# electronic_load.net
KiCad netlist of a schematic drawn in EAGLE
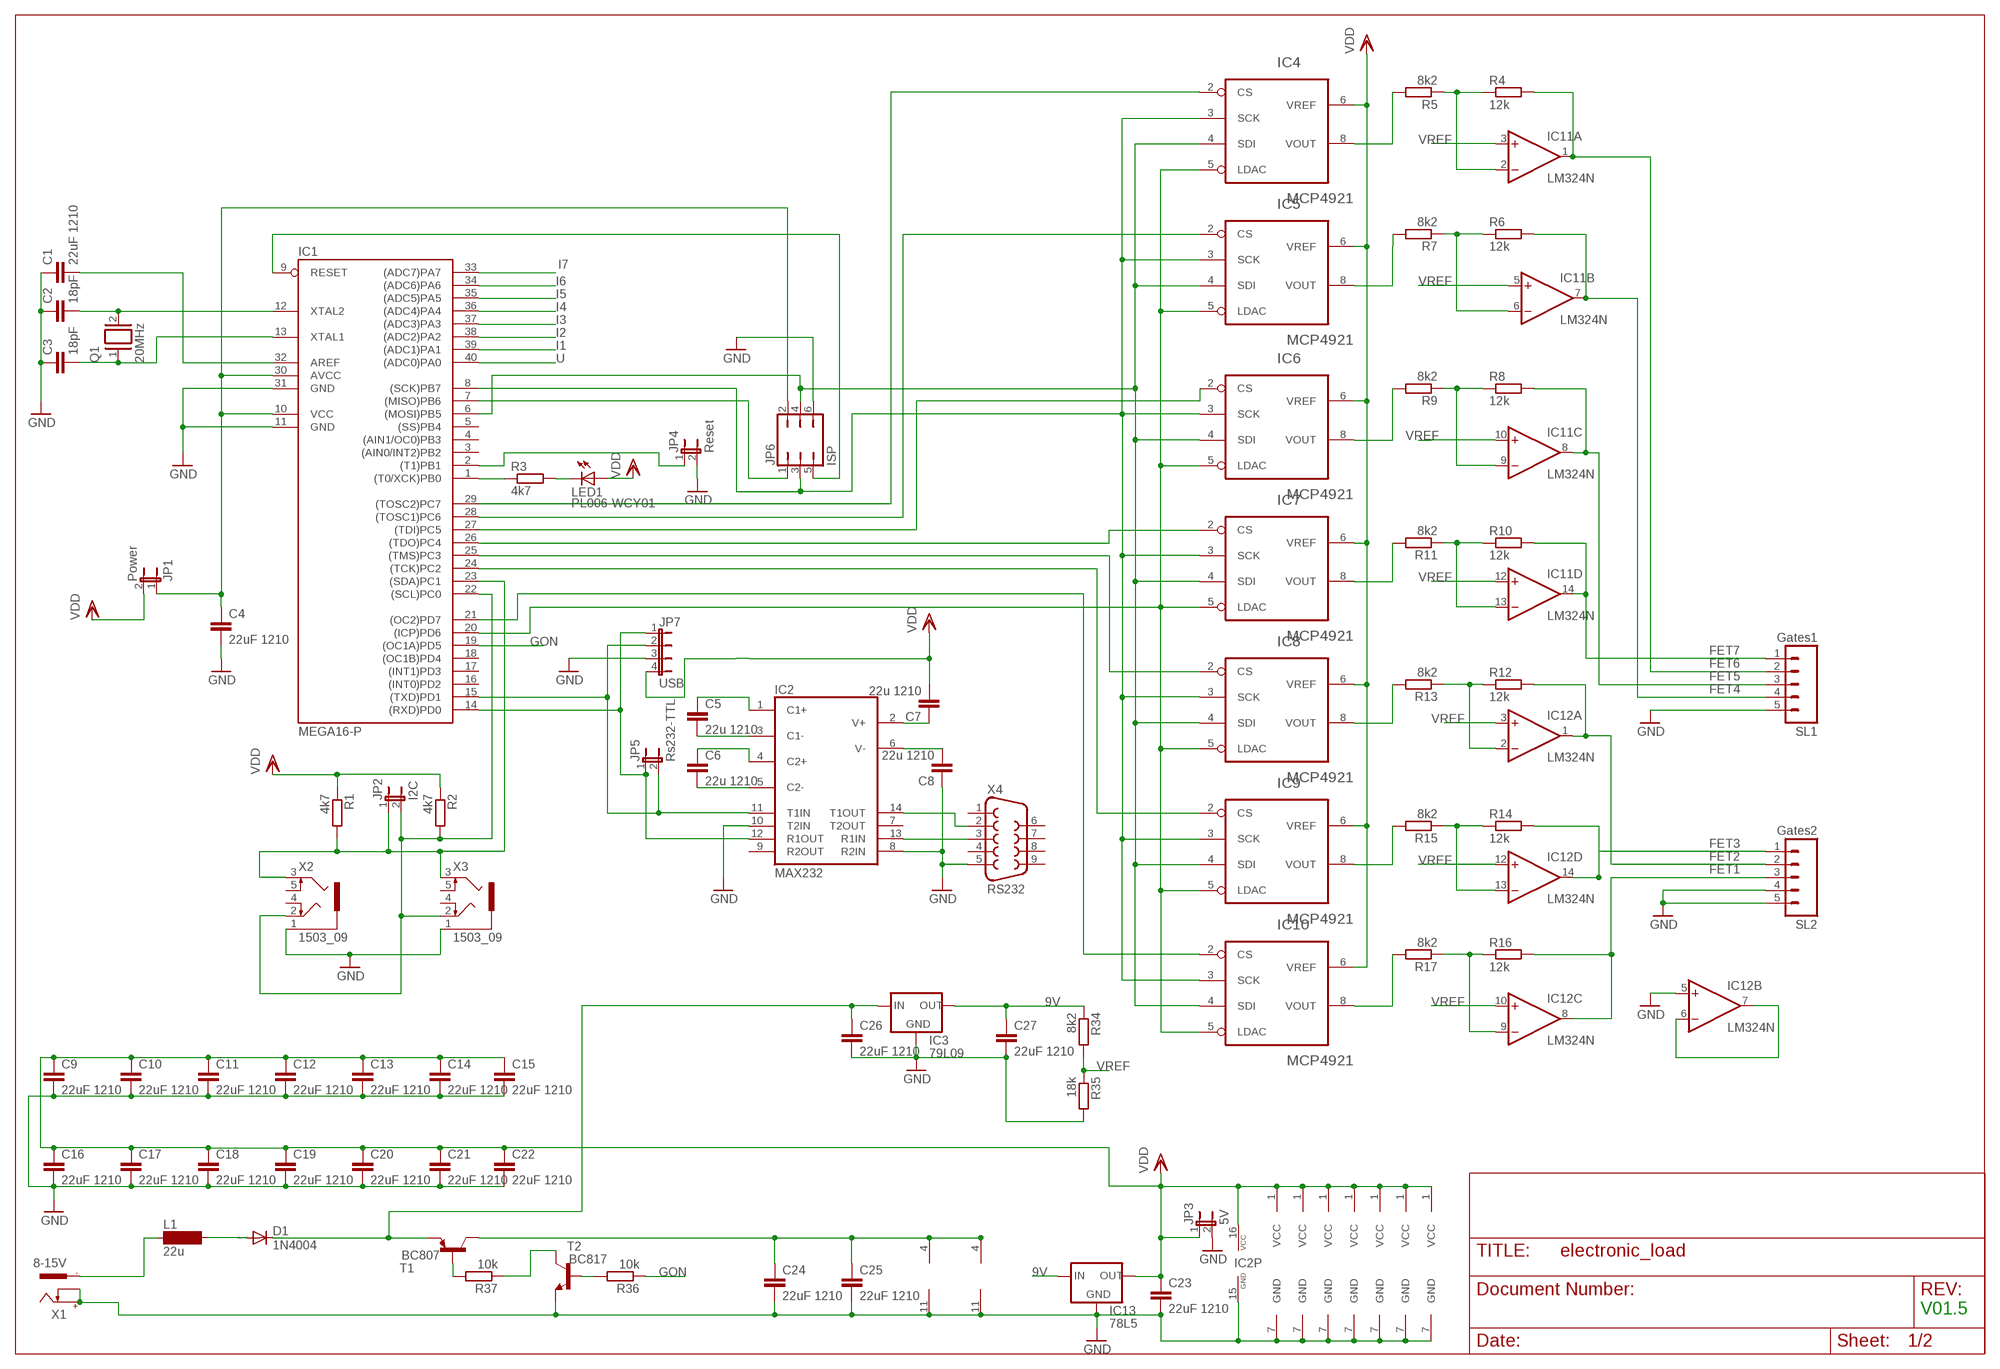
[diagram p0: schematic, sheet 1]
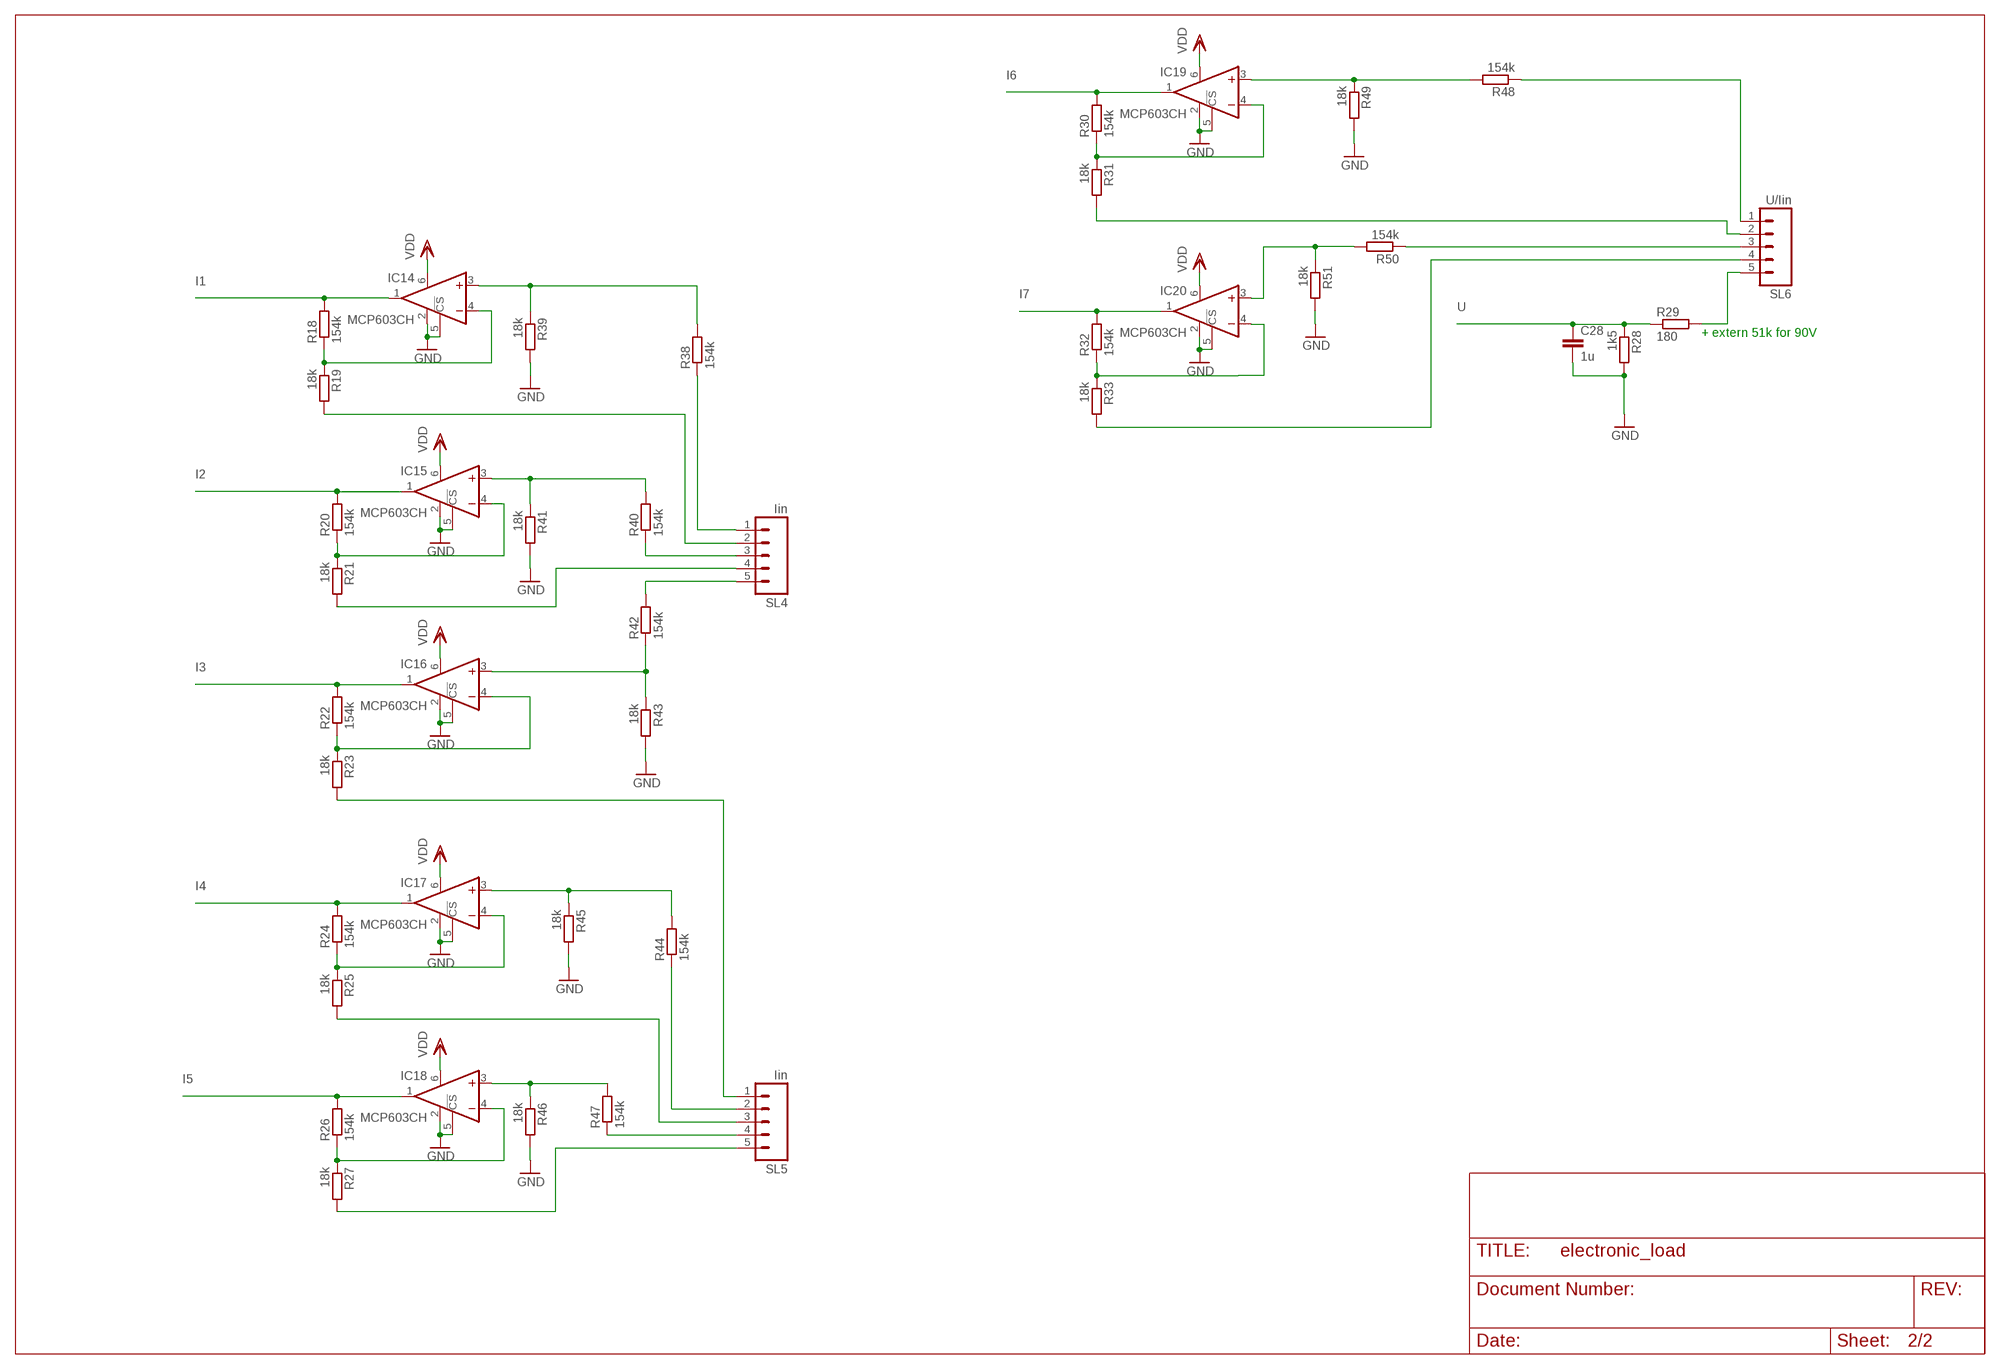
[diagram p1: schematic, sheet 2]

(export (version "E")
  (design (tool "Eeschema 10.0.6"))
  (components
    (comp (ref "C28")
      (value "1u")
      (footprint "eagle-import:C1206")
      (libsource (lib "eagle-import") (part "resistor_C-EUC1206"))
    )
    (comp (ref "IC14")
      (value "MCP603CH")
      (footprint "eagle-import:SOT23-6")
      (libsource (lib "eagle-import") (part "MCP603CH"))
    )
    (comp (ref "IC15")
      (value "MCP603CH")
      (footprint "eagle-import:SOT23-6")
      (libsource (lib "eagle-import") (part "MCP603CH"))
    )
    (comp (ref "IC16")
      (value "MCP603CH")
      (footprint "eagle-import:SOT23-6")
      (libsource (lib "eagle-import") (part "MCP603CH"))
    )
    (comp (ref "IC17")
      (value "MCP603CH")
      (footprint "eagle-import:SOT23-6")
      (libsource (lib "eagle-import") (part "MCP603CH"))
    )
    (comp (ref "IC18")
      (value "MCP603CH")
      (footprint "eagle-import:SOT23-6")
      (libsource (lib "eagle-import") (part "MCP603CH"))
    )
    (comp (ref "IC19")
      (value "MCP603CH")
      (footprint "eagle-import:SOT23-6")
      (libsource (lib "eagle-import") (part "MCP603CH"))
    )
    (comp (ref "IC20")
      (value "MCP603CH")
      (footprint "eagle-import:SOT23-6")
      (libsource (lib "eagle-import") (part "MCP603CH"))
    )
    (comp (ref "R18")
      (value "154k")
      (footprint "eagle-import:0207_2V")
      (libsource (lib "eagle-import") (part "R-EU_0207/2V"))
    )
    (comp (ref "R19")
      (value "18k")
      (footprint "eagle-import:0207_2V")
      (libsource (lib "eagle-import") (part "R-EU_0207/2V"))
    )
    (comp (ref "R20")
      (value "154k")
      (footprint "eagle-import:0207_2V")
      (libsource (lib "eagle-import") (part "R-EU_0207/2V"))
    )
    (comp (ref "R21")
      (value "18k")
      (footprint "eagle-import:0207_2V")
      (libsource (lib "eagle-import") (part "R-EU_0207/2V"))
    )
    (comp (ref "R22")
      (value "154k")
      (footprint "eagle-import:0207_2V")
      (libsource (lib "eagle-import") (part "R-EU_0207/2V"))
    )
    (comp (ref "R23")
      (value "18k")
      (footprint "eagle-import:0207_2V")
      (libsource (lib "eagle-import") (part "R-EU_0207/2V"))
    )
    (comp (ref "R24")
      (value "154k")
      (footprint "eagle-import:0207_2V")
      (libsource (lib "eagle-import") (part "R-EU_0207/2V"))
    )
    (comp (ref "R25")
      (value "18k")
      (footprint "eagle-import:0207_2V")
      (libsource (lib "eagle-import") (part "R-EU_0207/2V"))
    )
    (comp (ref "R26")
      (value "154k")
      (footprint "eagle-import:0207_2V")
      (libsource (lib "eagle-import") (part "R-EU_0207/2V"))
    )
    (comp (ref "R27")
      (value "18k")
      (footprint "eagle-import:0207_2V")
      (libsource (lib "eagle-import") (part "R-EU_0207/2V"))
    )
    (comp (ref "R28")
      (value "1k5")
      (footprint "eagle-import:R1206")
      (libsource (lib "eagle-import") (part "R-EU_R1206"))
    )
    (comp (ref "R29")
      (value "180")
      (footprint "eagle-import:R1206")
      (libsource (lib "eagle-import") (part "R-EU_R1206"))
    )
    (comp (ref "R30")
      (value "154k")
      (footprint "eagle-import:0207_2V")
      (libsource (lib "eagle-import") (part "R-EU_0207/2V"))
    )
    (comp (ref "R31")
      (value "18k")
      (footprint "eagle-import:0207_2V")
      (libsource (lib "eagle-import") (part "R-EU_0207/2V"))
    )
    (comp (ref "R32")
      (value "154k")
      (footprint "eagle-import:0207_2V")
      (libsource (lib "eagle-import") (part "R-EU_0207/2V"))
    )
    (comp (ref "R33")
      (value "18k")
      (footprint "eagle-import:0207_2V")
      (libsource (lib "eagle-import") (part "R-EU_0207/2V"))
    )
    (comp (ref "R38")
      (value "154k")
      (footprint "eagle-import:0207_2V")
      (libsource (lib "eagle-import") (part "R-EU_0207/2V"))
    )
    (comp (ref "R39")
      (value "18k")
      (footprint "eagle-import:0207_2V")
      (libsource (lib "eagle-import") (part "R-EU_0207/2V"))
    )
    (comp (ref "R40")
      (value "154k")
      (footprint "eagle-import:0207_2V")
      (libsource (lib "eagle-import") (part "R-EU_0207/2V"))
    )
    (comp (ref "R41")
      (value "18k")
      (footprint "eagle-import:0207_2V")
      (libsource (lib "eagle-import") (part "R-EU_0207/2V"))
    )
    (comp (ref "R42")
      (value "154k")
      (footprint "eagle-import:0207_2V")
      (libsource (lib "eagle-import") (part "R-EU_0207/2V"))
    )
    (comp (ref "R43")
      (value "18k")
      (footprint "eagle-import:0207_2V")
      (libsource (lib "eagle-import") (part "R-EU_0207/2V"))
    )
    (comp (ref "R44")
      (value "154k")
      (footprint "eagle-import:0207_2V")
      (libsource (lib "eagle-import") (part "R-EU_0207/2V"))
    )
    (comp (ref "R45")
      (value "18k")
      (footprint "eagle-import:0207_2V")
      (libsource (lib "eagle-import") (part "R-EU_0207/2V"))
    )
    (comp (ref "R46")
      (value "18k")
      (footprint "eagle-import:0207_2V")
      (libsource (lib "eagle-import") (part "R-EU_0207/2V"))
    )
    (comp (ref "R47")
      (value "154k")
      (footprint "eagle-import:0207_2V")
      (libsource (lib "eagle-import") (part "R-EU_0207/2V"))
    )
    (comp (ref "R48")
      (value "154k")
      (footprint "eagle-import:0207_2V")
      (libsource (lib "eagle-import") (part "R-EU_0207/2V"))
    )
    (comp (ref "R49")
      (value "18k")
      (footprint "eagle-import:0207_2V")
      (libsource (lib "eagle-import") (part "R-EU_0207/2V"))
    )
    (comp (ref "R50")
      (value "154k")
      (footprint "eagle-import:0207_2V")
      (libsource (lib "eagle-import") (part "R-EU_0207/2V"))
    )
    (comp (ref "R51")
      (value "18k")
      (footprint "eagle-import:0207_2V")
      (libsource (lib "eagle-import") (part "R-EU_0207/2V"))
    )
    (comp (ref "SL4")
      (value "Iin")
      (footprint "eagle-import:05P")
      (libsource (lib "eagle-import") (part "M05"))
    )
    (comp (ref "SL5")
      (value "Iin")
      (footprint "eagle-import:05P")
      (libsource (lib "eagle-import") (part "M05"))
    )
    (comp (ref "SL6")
      (value "U/Iin")
      (footprint "eagle-import:05P")
      (libsource (lib "eagle-import") (part "M05"))
    )
    (comp (ref "C1")
      (value "22uF 1210")
      (footprint "eagle-import:C1206")
      (libsource (lib "eagle-import") (part "C-EUC1206"))
    )
    (comp (ref "C2")
      (value "18pF")
      (footprint "eagle-import:C025-025X050")
      (libsource (lib "eagle-import") (part "resistor_C-EU025-025X050"))
    )
    (comp (ref "C3")
      (value "18pF")
      (footprint "eagle-import:C025-025X050")
      (libsource (lib "eagle-import") (part "resistor_C-EU025-025X050"))
    )
    (comp (ref "C4")
      (value "22uF 1210")
      (footprint "eagle-import:C1206")
      (libsource (lib "eagle-import") (part "C-EUC1206"))
    )
    (comp (ref "C5")
      (value "22u 1210")
      (footprint "eagle-import:C1206")
      (libsource (lib "eagle-import") (part "C-EUC1206"))
    )
    (comp (ref "C6")
      (value "22u 1210")
      (footprint "eagle-import:C1206")
      (libsource (lib "eagle-import") (part "C-EUC1206"))
    )
    (comp (ref "C7")
      (value "22u 1210")
      (footprint "eagle-import:C1206")
      (libsource (lib "eagle-import") (part "C-EUC1206"))
    )
    (comp (ref "C8")
      (value "22u 1210")
      (footprint "eagle-import:C1206")
      (libsource (lib "eagle-import") (part "C-EUC1206"))
    )
    (comp (ref "C9")
      (value "22uF 1210")
      (footprint "eagle-import:C1206")
      (libsource (lib "eagle-import") (part "C-EUC1206"))
    )
    (comp (ref "C10")
      (value "22uF 1210")
      (footprint "eagle-import:C1206")
      (libsource (lib "eagle-import") (part "C-EUC1206"))
    )
    (comp (ref "C11")
      (value "22uF 1210")
      (footprint "eagle-import:C1206")
      (libsource (lib "eagle-import") (part "C-EUC1206"))
    )
    (comp (ref "C12")
      (value "22uF 1210")
      (footprint "eagle-import:C1206")
      (libsource (lib "eagle-import") (part "C-EUC1206"))
    )
    (comp (ref "C13")
      (value "22uF 1210")
      (footprint "eagle-import:C1206")
      (libsource (lib "eagle-import") (part "C-EUC1206"))
    )
    (comp (ref "C14")
      (value "22uF 1210")
      (footprint "eagle-import:C1206")
      (libsource (lib "eagle-import") (part "C-EUC1206"))
    )
    (comp (ref "C15")
      (value "22uF 1210")
      (footprint "eagle-import:C1206")
      (libsource (lib "eagle-import") (part "C-EUC1206"))
    )
    (comp (ref "C16")
      (value "22uF 1210")
      (footprint "eagle-import:C1206")
      (libsource (lib "eagle-import") (part "C-EUC1206"))
    )
    (comp (ref "C17")
      (value "22uF 1210")
      (footprint "eagle-import:C1206")
      (libsource (lib "eagle-import") (part "C-EUC1206"))
    )
    (comp (ref "C18")
      (value "22uF 1210")
      (footprint "eagle-import:C1206")
      (libsource (lib "eagle-import") (part "C-EUC1206"))
    )
    (comp (ref "C19")
      (value "22uF 1210")
      (footprint "eagle-import:C1206")
      (libsource (lib "eagle-import") (part "C-EUC1206"))
    )
    (comp (ref "C20")
      (value "22uF 1210")
      (footprint "eagle-import:C1206")
      (libsource (lib "eagle-import") (part "C-EUC1206"))
    )
    (comp (ref "C21")
      (value "22uF 1210")
      (footprint "eagle-import:C1206")
      (libsource (lib "eagle-import") (part "C-EUC1206"))
    )
    (comp (ref "C22")
      (value "22uF 1210")
      (footprint "eagle-import:C1206")
      (libsource (lib "eagle-import") (part "C-EUC1206"))
    )
    (comp (ref "C23")
      (value "22uF 1210")
      (footprint "eagle-import:C1206")
      (libsource (lib "eagle-import") (part "C-EUC1206"))
    )
    (comp (ref "C24")
      (value "22uF 1210")
      (footprint "eagle-import:C1206")
      (libsource (lib "eagle-import") (part "C-EUC1206"))
    )
    (comp (ref "C25")
      (value "22uF 1210")
      (footprint "eagle-import:C1206")
      (libsource (lib "eagle-import") (part "C-EUC1206"))
    )
    (comp (ref "C26")
      (value "22uF 1210")
      (footprint "eagle-import:C1206")
      (libsource (lib "eagle-import") (part "C-EUC1206"))
    )
    (comp (ref "C27")
      (value "22uF 1210")
      (footprint "eagle-import:C1206")
      (libsource (lib "eagle-import") (part "C-EUC1206"))
    )
    (comp (ref "D1")
      (value "1N4004")
      (footprint "eagle-import:DO41-10")
      (libsource (lib "eagle-import") (part "1N4004"))
    )
    (comp (ref "IC1")
      (value "MEGA16-P")
      (footprint "eagle-import:DIL40")
      (fields (field (name "MPN") "ATMEGA16-16PU"))
      (libsource (lib "eagle-import") (part "MEGA16-P"))
    )
    (comp (ref "IC2")
      (value "MAX232")
      (footprint "eagle-import:DIL16")
      (fields (field (name "MF") "MAXIM") (field (name "MPN") "MAX232ACPE+"))
      (libsource (lib "eagle-import") (part "MAX232"))
    )
    (comp (ref "IC3")
      (value "79L09")
      (footprint "eagle-import:78LXX")
      (libsource (lib "eagle-import") (part "78LXX"))
    )
    (comp (ref "IC4")
      (value "MCP4921")
      (footprint "eagle-import:DIL08")
      (libsource (lib "eagle-import") (part "MCP491"))
    )
    (comp (ref "IC5")
      (value "MCP4921")
      (footprint "eagle-import:DIL08")
      (libsource (lib "eagle-import") (part "MCP491"))
    )
    (comp (ref "IC6")
      (value "MCP4921")
      (footprint "eagle-import:DIL08")
      (libsource (lib "eagle-import") (part "MCP491"))
    )
    (comp (ref "IC7")
      (value "MCP4921")
      (footprint "eagle-import:DIL08")
      (libsource (lib "eagle-import") (part "MCP491"))
    )
    (comp (ref "IC8")
      (value "MCP4921")
      (footprint "eagle-import:DIL08")
      (libsource (lib "eagle-import") (part "MCP491"))
    )
    (comp (ref "IC9")
      (value "MCP4921")
      (footprint "eagle-import:DIL08")
      (libsource (lib "eagle-import") (part "MCP491"))
    )
    (comp (ref "IC10")
      (value "MCP4921")
      (footprint "eagle-import:DIL08")
      (libsource (lib "eagle-import") (part "MCP491"))
    )
    (comp (ref "IC11")
      (value "LM324N")
      (footprint "eagle-import:DIL14")
      (libsource (lib "eagle-import") (part "LM324N"))
    )
    (comp (ref "IC12")
      (value "LM324N")
      (footprint "eagle-import:DIL14")
      (libsource (lib "eagle-import") (part "LM324N"))
    )
    (comp (ref "IC13")
      (value "78L5")
      (footprint "eagle-import:78LXX")
      (libsource (lib "eagle-import") (part "78LXX"))
    )
    (comp (ref "JP1")
      (value "Power")
      (footprint "eagle-import:JP1")
      (libsource (lib "eagle-import") (part "JP1E"))
    )
    (comp (ref "JP2")
      (value "I2C")
      (footprint "eagle-import:JP1")
      (libsource (lib "eagle-import") (part "JP1E"))
    )
    (comp (ref "JP3")
      (value "5V")
      (footprint "eagle-import:JP1")
      (libsource (lib "eagle-import") (part "JP1E"))
    )
    (comp (ref "JP4")
      (value "Reset")
      (footprint "eagle-import:JP1")
      (libsource (lib "eagle-import") (part "JP1E"))
    )
    (comp (ref "JP5")
      (value "Rs232-TTL")
      (footprint "eagle-import:JP1")
      (libsource (lib "eagle-import") (part "JP1E"))
    )
    (comp (ref "JP6")
      (value "ISP")
      (footprint "eagle-import:JP3Q")
      (libsource (lib "eagle-import") (part "JP3Q"))
    )
    (comp (ref "JP7")
      (value "USB")
      (footprint "eagle-import:JP4")
      (libsource (lib "eagle-import") (part "JP4E"))
    )
    (comp (ref "L1")
      (value "22u")
      (footprint "eagle-import:MS85")
      (libsource (lib "eagle-import") (part "MS85"))
    )
    (comp (ref "LED1")
      (value "PL006-WCY01")
      (footprint "eagle-import:SOT23")
      (libsource (lib "eagle-import") (part "PL006-WCY01"))
    )
    (comp (ref "Q1")
      (value "20MHz")
      (footprint "eagle-import:QS")
      (libsource (lib "eagle-import") (part "XTAL/S"))
    )
    (comp (ref "R1")
      (value "4k7")
      (footprint "eagle-import:0207_2V")
      (libsource (lib "eagle-import") (part "R-EU_0207/2V"))
    )
    (comp (ref "R2")
      (value "4k7")
      (footprint "eagle-import:0207_2V")
      (libsource (lib "eagle-import") (part "R-EU_0207/2V"))
    )
    (comp (ref "R3")
      (value "4k7")
      (footprint "eagle-import:R1206")
      (libsource (lib "eagle-import") (part "R-EU_R1206"))
    )
    (comp (ref "R4")
      (value "12k")
      (footprint "eagle-import:R1206")
      (libsource (lib "eagle-import") (part "R-EU_R1206"))
    )
    (comp (ref "R5")
      (value "8k2")
      (footprint "eagle-import:R1206")
      (libsource (lib "eagle-import") (part "R-EU_R1206"))
    )
    (comp (ref "R6")
      (value "12k")
      (footprint "eagle-import:R1206")
      (libsource (lib "eagle-import") (part "R-EU_R1206"))
    )
    (comp (ref "R7")
      (value "8k2")
      (footprint "eagle-import:R1206")
      (libsource (lib "eagle-import") (part "R-EU_R1206"))
    )
    (comp (ref "R8")
      (value "12k")
      (footprint "eagle-import:R1206")
      (libsource (lib "eagle-import") (part "R-EU_R1206"))
    )
    (comp (ref "R9")
      (value "8k2")
      (footprint "eagle-import:R1206")
      (libsource (lib "eagle-import") (part "R-EU_R1206"))
    )
    (comp (ref "R10")
      (value "12k")
      (footprint "eagle-import:R1206")
      (libsource (lib "eagle-import") (part "R-EU_R1206"))
    )
    (comp (ref "R11")
      (value "8k2")
      (footprint "eagle-import:R1206")
      (libsource (lib "eagle-import") (part "R-EU_R1206"))
    )
    (comp (ref "R12")
      (value "12k")
      (footprint "eagle-import:R1206")
      (libsource (lib "eagle-import") (part "R-EU_R1206"))
    )
    (comp (ref "R13")
      (value "8k2")
      (footprint "eagle-import:R1206")
      (libsource (lib "eagle-import") (part "R-EU_R1206"))
    )
    (comp (ref "R14")
      (value "12k")
      (footprint "eagle-import:R1206")
      (libsource (lib "eagle-import") (part "R-EU_R1206"))
    )
    (comp (ref "R15")
      (value "8k2")
      (footprint "eagle-import:R1206")
      (libsource (lib "eagle-import") (part "R-EU_R1206"))
    )
    (comp (ref "R16")
      (value "12k")
      (footprint "eagle-import:R1206")
      (libsource (lib "eagle-import") (part "R-EU_R1206"))
    )
    (comp (ref "R17")
      (value "8k2")
      (footprint "eagle-import:R1206")
      (libsource (lib "eagle-import") (part "R-EU_R1206"))
    )
    (comp (ref "R34")
      (value "8k2")
      (footprint "eagle-import:R1206")
      (libsource (lib "eagle-import") (part "R-EU_R1206"))
    )
    (comp (ref "R35")
      (value "18k")
      (footprint "eagle-import:R1206")
      (libsource (lib "eagle-import") (part "R-EU_R1206"))
    )
    (comp (ref "R36")
      (value "10k")
      (footprint "eagle-import:R1206")
      (libsource (lib "eagle-import") (part "R-EU_R1206"))
    )
    (comp (ref "R37")
      (value "10k")
      (footprint "eagle-import:R1206")
      (libsource (lib "eagle-import") (part "R-EU_R1206"))
    )
    (comp (ref "SL1")
      (value "Gates1")
      (footprint "eagle-import:05P")
      (libsource (lib "eagle-import") (part "M05"))
    )
    (comp (ref "SL2")
      (value "Gates2")
      (footprint "eagle-import:05P")
      (libsource (lib "eagle-import") (part "M05"))
    )
    (comp (ref "T1")
      (value "BC807")
      (footprint "eagle-import:SOT23-BEC")
      (libsource (lib "eagle-import") (part "-PNP-SOT23-BECBC807-16"))
    )
    (comp (ref "T2")
      (value "BC817")
      (footprint "eagle-import:SOT23-BEC")
      (libsource (lib "eagle-import") (part "-NPN-SOT23-BECBC817-16"))
    )
    (comp (ref "X1")
      (value "8-15V")
      (footprint "eagle-import:737992-5")
      (libsource (lib "eagle-import") (part "737992-55"))
    )
    (comp (ref "X2")
      (value "1503_09")
      (footprint "eagle-import:1503_09")
      (libsource (lib "eagle-import") (part "1503_09"))
    )
    (comp (ref "X3")
      (value "1503_09")
      (footprint "eagle-import:1503_09")
      (libsource (lib "eagle-import") (part "1503_09"))
    )
    (comp (ref "X4")
      (value "RS232")
      (footprint "eagle-import:F09H")
      (libsource (lib "eagle-import") (part "F09H"))
    )
  )
  (nets
    (net (code "1") (name "9V") (class "Default")
      (node (ref "C27") (pin "1") (pinfunction "1_1") (pintype "passive"))
      (node (ref "IC13") (pin "IN") (pinfunction "IN_IN") (pintype "input"))
      (node (ref "IC3") (pin "OUT") (pinfunction "OUT_OUT") (pintype "passive"))
      (node (ref "R34") (pin "1") (pinfunction "1_1") (pintype "passive"))
    )
    (net (code "2") (name "FET1") (class "Default")
      (node (ref "IC12") (pin "8") (pinfunction "OUT_8") (pintype "output"))
      (node (ref "R16") (pin "2") (pinfunction "2_2") (pintype "passive"))
      (node (ref "SL2") (pin "3") (pinfunction "3_3") (pintype "passive"))
    )
    (net (code "3") (name "FET2") (class "Default")
      (node (ref "IC12") (pin "1") (pinfunction "OUT_1") (pintype "output"))
      (node (ref "R12") (pin "2") (pinfunction "2_2") (pintype "passive"))
      (node (ref "SL2") (pin "2") (pinfunction "2_2") (pintype "passive"))
    )
    (net (code "4") (name "FET3") (class "Default")
      (node (ref "IC12") (pin "14") (pinfunction "OUT_14") (pintype "output"))
      (node (ref "R14") (pin "2") (pinfunction "2_2") (pintype "passive"))
      (node (ref "SL2") (pin "1") (pinfunction "1_1") (pintype "passive"))
    )
    (net (code "5") (name "FET4") (class "Default")
      (node (ref "IC11") (pin "7") (pinfunction "OUT_7") (pintype "output"))
      (node (ref "R6") (pin "2") (pinfunction "2_2") (pintype "passive"))
      (node (ref "SL1") (pin "4") (pinfunction "4_4") (pintype "passive"))
    )
    (net (code "6") (name "FET5") (class "Default")
      (node (ref "IC11") (pin "8") (pinfunction "OUT_8") (pintype "output"))
      (node (ref "R8") (pin "2") (pinfunction "2_2") (pintype "passive"))
      (node (ref "SL1") (pin "3") (pinfunction "3_3") (pintype "passive"))
    )
    (net (code "7") (name "FET6") (class "Default")
      (node (ref "IC11") (pin "1") (pinfunction "OUT_1") (pintype "output"))
      (node (ref "R4") (pin "2") (pinfunction "2_2") (pintype "passive"))
      (node (ref "SL1") (pin "2") (pinfunction "2_2") (pintype "passive"))
    )
    (net (code "8") (name "FET7") (class "Default")
      (node (ref "IC11") (pin "14") (pinfunction "OUT_14") (pintype "output"))
      (node (ref "R10") (pin "2") (pinfunction "2_2") (pintype "passive"))
      (node (ref "SL1") (pin "1") (pinfunction "1_1") (pintype "passive"))
    )
    (net (code "9") (name "GND") (class "Default")
      (node (ref "C1") (pin "1") (pinfunction "1_1") (pintype "passive"))
      (node (ref "C10") (pin "2") (pinfunction "2_2") (pintype "passive"))
      (node (ref "C11") (pin "2") (pinfunction "2_2") (pintype "passive"))
      (node (ref "C12") (pin "2") (pinfunction "2_2") (pintype "passive"))
      (node (ref "C13") (pin "2") (pinfunction "2_2") (pintype "passive"))
      (node (ref "C14") (pin "2") (pinfunction "2_2") (pintype "passive"))
      (node (ref "C15") (pin "2") (pinfunction "2_2") (pintype "passive"))
      (node (ref "C16") (pin "2") (pinfunction "2_2") (pintype "passive"))
      (node (ref "C17") (pin "2") (pinfunction "2_2") (pintype "passive"))
      (node (ref "C18") (pin "2") (pinfunction "2_2") (pintype "passive"))
      (node (ref "C19") (pin "2") (pinfunction "2_2") (pintype "passive"))
      (node (ref "C2") (pin "1") (pinfunction "1_1") (pintype "passive"))
      (node (ref "C20") (pin "2") (pinfunction "2_2") (pintype "passive"))
      (node (ref "C21") (pin "2") (pinfunction "2_2") (pintype "passive"))
      (node (ref "C22") (pin "2") (pinfunction "2_2") (pintype "passive"))
      (node (ref "C23") (pin "2") (pinfunction "2_2") (pintype "passive"))
      (node (ref "C24") (pin "2") (pinfunction "2_2") (pintype "passive"))
      (node (ref "C25") (pin "2") (pinfunction "2_2") (pintype "passive"))
      (node (ref "C26") (pin "2") (pinfunction "2_2") (pintype "passive"))
      (node (ref "C27") (pin "2") (pinfunction "2_2") (pintype "passive"))
      (node (ref "C28") (pin "2") (pinfunction "2_2") (pintype "passive"))
      (node (ref "C3") (pin "1") (pinfunction "1_1") (pintype "passive"))
      (node (ref "C4") (pin "2") (pinfunction "2_2") (pintype "passive"))
      (node (ref "C8") (pin "1") (pinfunction "1_1") (pintype "passive"))
      (node (ref "C9") (pin "2") (pinfunction "2_2") (pintype "passive"))
      (node (ref "IC1") (pin "11") (pinfunction "GND_11") (pintype "power_in"))
      (node (ref "IC1") (pin "31") (pinfunction "GND_31") (pintype "power_in"))
      (node (ref "IC10") (pin "7") (pinfunction "GND_7") (pintype "power_in"))
      (node (ref "IC11") (pin "11") (pinfunction "V-_11") (pintype "power_in"))
      (node (ref "IC12") (pin "11") (pinfunction "V-_11") (pintype "power_in"))
      (node (ref "IC12") (pin "5") (pinfunction "+IN_5") (pintype "input"))
      (node (ref "IC13") (pin "GND") (pinfunction "GND_GND") (pintype "input"))
      (node (ref "IC14") (pin "2") (pinfunction "V-_2") (pintype "power_in"))
      (node (ref "IC14") (pin "5") (pinfunction "~{CS}_5") (pintype "input"))
      (node (ref "IC15") (pin "2") (pinfunction "V-_2") (pintype "power_in"))
      (node (ref "IC15") (pin "5") (pinfunction "~{CS}_5") (pintype "input"))
      (node (ref "IC16") (pin "2") (pinfunction "V-_2") (pintype "power_in"))
      (node (ref "IC16") (pin "5") (pinfunction "~{CS}_5") (pintype "input"))
      (node (ref "IC17") (pin "2") (pinfunction "V-_2") (pintype "power_in"))
      (node (ref "IC17") (pin "5") (pinfunction "~{CS}_5") (pintype "input"))
      (node (ref "IC18") (pin "2") (pinfunction "V-_2") (pintype "power_in"))
      (node (ref "IC18") (pin "5") (pinfunction "~{CS}_5") (pintype "input"))
      (node (ref "IC19") (pin "2") (pinfunction "V-_2") (pintype "power_in"))
      (node (ref "IC19") (pin "5") (pinfunction "~{CS}_5") (pintype "input"))
      (node (ref "IC2") (pin "10") (pinfunction "T2IN_10") (pintype "input"))
      (node (ref "IC2") (pin "15") (pinfunction "GND_15") (pintype "power_in"))
      (node (ref "IC2") (pin "8") (pinfunction "R2IN_8") (pintype "input"))
      (node (ref "IC20") (pin "2") (pinfunction "V-_2") (pintype "power_in"))
      (node (ref "IC20") (pin "5") (pinfunction "~{CS}_5") (pintype "input"))
      (node (ref "IC3") (pin "GND") (pinfunction "GND_GND") (pintype "input"))
      (node (ref "IC4") (pin "7") (pinfunction "GND_7") (pintype "power_in"))
      (node (ref "IC5") (pin "7") (pinfunction "GND_7") (pintype "power_in"))
      (node (ref "IC6") (pin "7") (pinfunction "GND_7") (pintype "power_in"))
      (node (ref "IC7") (pin "7") (pinfunction "GND_7") (pintype "power_in"))
      (node (ref "IC8") (pin "7") (pinfunction "GND_7") (pintype "power_in"))
      (node (ref "IC9") (pin "7") (pinfunction "GND_7") (pintype "power_in"))
      (node (ref "JP3") (pin "2") (pinfunction "2_2") (pintype "passive"))
      (node (ref "JP4") (pin "2") (pinfunction "2_2") (pintype "passive"))
      (node (ref "JP6") (pin "6") (pinfunction "6_6") (pintype "passive"))
      (node (ref "JP7") (pin "3") (pinfunction "3_3") (pintype "passive"))
      (node (ref "R28") (pin "2") (pinfunction "2_2") (pintype "passive"))
      (node (ref "R35") (pin "2") (pinfunction "2_2") (pintype "passive"))
      (node (ref "R39") (pin "2") (pinfunction "2_2") (pintype "passive"))
      (node (ref "R41") (pin "2") (pinfunction "2_2") (pintype "passive"))
      (node (ref "R43") (pin "2") (pinfunction "2_2") (pintype "passive"))
      (node (ref "R45") (pin "2") (pinfunction "2_2") (pintype "passive"))
      (node (ref "R46") (pin "2") (pinfunction "2_2") (pintype "passive"))
      (node (ref "R49") (pin "2") (pinfunction "2_2") (pintype "passive"))
      (node (ref "R51") (pin "2") (pinfunction "2_2") (pintype "passive"))
      (node (ref "SL1") (pin "5") (pinfunction "5_5") (pintype "passive"))
      (node (ref "SL2") (pin "4") (pinfunction "4_4") (pintype "passive"))
      (node (ref "SL2") (pin "5") (pinfunction "5_5") (pintype "passive"))
      (node (ref "T2") (pin "E") (pinfunction "E_E") (pintype "passive"))
      (node (ref "X1") (pin "+") (pinfunction "+_+") (pintype "passive"))
      (node (ref "X1") (pin "K") (pinfunction "K_K") (pintype "passive"))
      (node (ref "X2") (pin "1") (pinfunction "1_1") (pintype "passive"))
      (node (ref "X3") (pin "1") (pinfunction "1_1") (pintype "passive"))
      (node (ref "X4") (pin "5") (pinfunction "5_5") (pintype "passive"))
    )
    (net (code "10") (name "GON") (class "Default")
      (node (ref "IC1") (pin "19") (pinfunction "(OC1A)PD5_19") (pintype "bidirectional"))
      (node (ref "R36") (pin "1") (pinfunction "1_1") (pintype "passive"))
    )
    (net (code "11") (name "I1") (class "Default")
      (node (ref "IC1") (pin "39") (pinfunction "(ADC1)PA1_39") (pintype "bidirectional"))
      (node (ref "IC14") (pin "1") (pinfunction "OUT_1") (pintype "output"))
      (node (ref "R18") (pin "2") (pinfunction "2_2") (pintype "passive"))
    )
    (net (code "12") (name "I2") (class "Default")
      (node (ref "IC1") (pin "38") (pinfunction "(ADC2)PA2_38") (pintype "bidirectional"))
      (node (ref "IC15") (pin "1") (pinfunction "OUT_1") (pintype "output"))
      (node (ref "R20") (pin "2") (pinfunction "2_2") (pintype "passive"))
    )
    (net (code "13") (name "I3") (class "Default")
      (node (ref "IC1") (pin "37") (pinfunction "(ADC3)PA3_37") (pintype "bidirectional"))
      (node (ref "IC16") (pin "1") (pinfunction "OUT_1") (pintype "output"))
      (node (ref "R22") (pin "2") (pinfunction "2_2") (pintype "passive"))
    )
    (net (code "14") (name "I4") (class "Default")
      (node (ref "IC1") (pin "36") (pinfunction "(ADC4)PA4_36") (pintype "bidirectional"))
      (node (ref "IC17") (pin "1") (pinfunction "OUT_1") (pintype "output"))
      (node (ref "R24") (pin "2") (pinfunction "2_2") (pintype "passive"))
    )
    (net (code "15") (name "I5") (class "Default")
      (node (ref "IC1") (pin "35") (pinfunction "(ADC5)PA5_35") (pintype "bidirectional"))
      (node (ref "IC18") (pin "1") (pinfunction "OUT_1") (pintype "output"))
      (node (ref "R26") (pin "2") (pinfunction "2_2") (pintype "passive"))
    )
    (net (code "16") (name "I6") (class "Default")
      (node (ref "IC1") (pin "34") (pinfunction "(ADC6)PA6_34") (pintype "bidirectional"))
      (node (ref "IC19") (pin "1") (pinfunction "OUT_1") (pintype "output"))
      (node (ref "R30") (pin "2") (pinfunction "2_2") (pintype "passive"))
    )
    (net (code "17") (name "I7") (class "Default")
      (node (ref "IC1") (pin "33") (pinfunction "(ADC7)PA7_33") (pintype "bidirectional"))
      (node (ref "IC20") (pin "1") (pinfunction "OUT_1") (pintype "output"))
      (node (ref "R32") (pin "2") (pinfunction "2_2") (pintype "passive"))
    )
    (net (code "18") (name "Net-(C26-Pad1)") (class "Default")
      (node (ref "C26") (pin "1") (pinfunction "1_1") (pintype "passive"))
      (node (ref "D1") (pin "C") (pinfunction "C_C") (pintype "passive"))
      (node (ref "IC3") (pin "IN") (pinfunction "IN_IN") (pintype "input"))
      (node (ref "T1") (pin "E") (pinfunction "E_E") (pintype "passive"))
    )
    (net (code "19") (name "Net-(D1-PadA)") (class "Default")
      (node (ref "D1") (pin "A") (pinfunction "A_A") (pintype "passive"))
      (node (ref "L1") (pin "2") (pinfunction "2_2") (pintype "passive"))
    )
    (net (code "20") (name "Net-(IC1-(ICP)PD6)") (class "Default")
      (node (ref "IC1") (pin "20") (pinfunction "(ICP)PD6_20") (pintype "bidirectional"))
      (node (ref "IC10") (pin "5") (pinfunction "LDAC_5") (pintype "input"))
      (node (ref "IC4") (pin "5") (pinfunction "LDAC_5") (pintype "input"))
      (node (ref "IC5") (pin "5") (pinfunction "LDAC_5") (pintype "input"))
      (node (ref "IC6") (pin "5") (pinfunction "LDAC_5") (pintype "input"))
      (node (ref "IC7") (pin "5") (pinfunction "LDAC_5") (pintype "input"))
      (node (ref "IC8") (pin "5") (pinfunction "LDAC_5") (pintype "input"))
      (node (ref "IC9") (pin "5") (pinfunction "LDAC_5") (pintype "input"))
    )
    (net (code "21") (name "Net-(IC1-(MISO)PB6)") (class "Default")
      (node (ref "IC1") (pin "7") (pinfunction "(MISO)PB6_7") (pintype "bidirectional"))
      (node (ref "JP6") (pin "1") (pinfunction "1_1") (pintype "passive"))
    )
    (net (code "22") (name "Net-(IC1-(MOSI)PB5)") (class "Default")
      (node (ref "IC1") (pin "6") (pinfunction "(MOSI)PB5_6") (pintype "bidirectional"))
      (node (ref "IC10") (pin "4") (pinfunction "SDI_4") (pintype "input"))
      (node (ref "IC4") (pin "4") (pinfunction "SDI_4") (pintype "input"))
      (node (ref "IC5") (pin "4") (pinfunction "SDI_4") (pintype "input"))
      (node (ref "IC6") (pin "4") (pinfunction "SDI_4") (pintype "input"))
      (node (ref "IC7") (pin "4") (pinfunction "SDI_4") (pintype "input"))
      (node (ref "IC8") (pin "4") (pinfunction "SDI_4") (pintype "input"))
      (node (ref "IC9") (pin "4") (pinfunction "SDI_4") (pintype "input"))
      (node (ref "JP6") (pin "4") (pinfunction "4_4") (pintype "passive"))
    )
    (net (code "23") (name "Net-(IC1-(OC2)PD7)") (class "Default")
      (node (ref "IC1") (pin "21") (pinfunction "(OC2)PD7_21") (pintype "bidirectional"))
      (node (ref "IC10") (pin "2") (pinfunction "CS_2") (pintype "input"))
    )
    (net (code "24") (name "Net-(IC1-(RXD)PD0)") (class "Default")
      (node (ref "IC1") (pin "14") (pinfunction "(RXD)PD0_14") (pintype "bidirectional"))
      (node (ref "IC2") (pin "12") (pinfunction "R1OUT_12") (pintype "output"))
      (node (ref "JP5") (pin "1") (pinfunction "1_1") (pintype "passive"))
      (node (ref "JP7") (pin "1") (pinfunction "1_1") (pintype "passive"))
    )
    (net (code "25") (name "Net-(IC1-(SCK)PB7)") (class "Default")
      (node (ref "IC1") (pin "8") (pinfunction "(SCK)PB7_8") (pintype "bidirectional"))
      (node (ref "IC10") (pin "3") (pinfunction "SCK_3") (pintype "input"))
      (node (ref "IC4") (pin "3") (pinfunction "SCK_3") (pintype "input"))
      (node (ref "IC5") (pin "3") (pinfunction "SCK_3") (pintype "input"))
      (node (ref "IC6") (pin "3") (pinfunction "SCK_3") (pintype "input"))
      (node (ref "IC7") (pin "3") (pinfunction "SCK_3") (pintype "input"))
      (node (ref "IC8") (pin "3") (pinfunction "SCK_3") (pintype "input"))
      (node (ref "IC9") (pin "3") (pinfunction "SCK_3") (pintype "input"))
      (node (ref "JP6") (pin "3") (pinfunction "3_3") (pintype "passive"))
    )
    (net (code "26") (name "Net-(IC1-(SCL)PC0)") (class "Default")
      (node (ref "IC1") (pin "22") (pinfunction "(SCL)PC0_22") (pintype "bidirectional"))
      (node (ref "JP2") (pin "2") (pinfunction "2_2") (pintype "passive"))
      (node (ref "R2") (pin "2") (pinfunction "2_2") (pintype "passive"))
      (node (ref "X2") (pin "2") (pinfunction "2_2") (pintype "passive"))
      (node (ref "X3") (pin "2") (pinfunction "2_2") (pintype "passive"))
    )
    (net (code "27") (name "Net-(IC1-(SDA)PC1)") (class "Default")
      (node (ref "IC1") (pin "23") (pinfunction "(SDA)PC1_23") (pintype "bidirectional"))
      (node (ref "JP2") (pin "1") (pinfunction "1_1") (pintype "passive"))
      (node (ref "R1") (pin "2") (pinfunction "2_2") (pintype "passive"))
      (node (ref "X2") (pin "3") (pinfunction "3_3") (pintype "passive"))
      (node (ref "X3") (pin "3") (pinfunction "3_3") (pintype "passive"))
    )
    (net (code "28") (name "Net-(IC1-(T0{slash}XCK)PB0)") (class "Default")
      (node (ref "IC1") (pin "1") (pinfunction "(T0/XCK)PB0_1") (pintype "bidirectional"))
      (node (ref "R3") (pin "1") (pinfunction "1_1") (pintype "passive"))
    )
    (net (code "29") (name "Net-(IC1-(T1)PB1)") (class "Default")
      (node (ref "IC1") (pin "2") (pinfunction "(T1)PB1_2") (pintype "bidirectional"))
      (node (ref "JP4") (pin "1") (pinfunction "1_1") (pintype "passive"))
    )
    (net (code "30") (name "Net-(IC1-(TCK)PC2)") (class "Default")
      (node (ref "IC1") (pin "24") (pinfunction "(TCK)PC2_24") (pintype "bidirectional"))
      (node (ref "IC9") (pin "2") (pinfunction "CS_2") (pintype "input"))
    )
    (net (code "31") (name "Net-(IC1-(TDI)PC5)") (class "Default")
      (node (ref "IC1") (pin "27") (pinfunction "(TDI)PC5_27") (pintype "bidirectional"))
      (node (ref "IC6") (pin "2") (pinfunction "CS_2") (pintype "input"))
    )
    (net (code "32") (name "Net-(IC1-(TDO)PC4)") (class "Default")
      (node (ref "IC1") (pin "26") (pinfunction "(TDO)PC4_26") (pintype "bidirectional"))
      (node (ref "IC7") (pin "2") (pinfunction "CS_2") (pintype "input"))
    )
    (net (code "33") (name "Net-(IC1-(TMS)PC3)") (class "Default")
      (node (ref "IC1") (pin "25") (pinfunction "(TMS)PC3_25") (pintype "bidirectional"))
      (node (ref "IC8") (pin "2") (pinfunction "CS_2") (pintype "input"))
    )
    (net (code "34") (name "Net-(IC1-(TOSC1)PC6)") (class "Default")
      (node (ref "IC1") (pin "28") (pinfunction "(TOSC1)PC6_28") (pintype "bidirectional"))
      (node (ref "IC5") (pin "2") (pinfunction "CS_2") (pintype "input"))
    )
    (net (code "35") (name "Net-(IC1-(TOSC2)PC7)") (class "Default")
      (node (ref "IC1") (pin "29") (pinfunction "(TOSC2)PC7_29") (pintype "bidirectional"))
      (node (ref "IC4") (pin "2") (pinfunction "CS_2") (pintype "input"))
    )
    (net (code "36") (name "Net-(IC1-(TXD)PD1)") (class "Default")
      (node (ref "IC1") (pin "15") (pinfunction "(TXD)PD1_15") (pintype "bidirectional"))
      (node (ref "IC2") (pin "11") (pinfunction "T1IN_11") (pintype "input"))
      (node (ref "JP5") (pin "2") (pinfunction "2_2") (pintype "passive"))
      (node (ref "JP7") (pin "2") (pinfunction "2_2") (pintype "passive"))
    )
    (net (code "37") (name "Net-(IC1-AREF)") (class "Default")
      (node (ref "C1") (pin "2") (pinfunction "2_2") (pintype "passive"))
      (node (ref "IC1") (pin "32") (pinfunction "AREF_32") (pintype "passive"))
    )
    (net (code "38") (name "Net-(IC1-AVCC)") (class "Default")
      (node (ref "C4") (pin "1") (pinfunction "1_1") (pintype "passive"))
      (node (ref "IC1") (pin "10") (pinfunction "VCC_10") (pintype "power_in"))
      (node (ref "IC1") (pin "30") (pinfunction "AVCC_30") (pintype "power_in"))
      (node (ref "JP1") (pin "1") (pinfunction "1_1") (pintype "passive"))
      (node (ref "JP6") (pin "2") (pinfunction "2_2") (pintype "passive"))
    )
    (net (code "39") (name "Net-(IC1-RESET)") (class "Default")
      (node (ref "IC1") (pin "9") (pinfunction "RESET_9") (pintype "input"))
      (node (ref "JP6") (pin "5") (pinfunction "5_5") (pintype "passive"))
    )
    (net (code "40") (name "Net-(IC1-XTAL1)") (class "Default")
      (node (ref "C3") (pin "2") (pinfunction "2_2") (pintype "passive"))
      (node (ref "IC1") (pin "13") (pinfunction "XTAL1_13") (pintype "bidirectional"))
      (node (ref "Q1") (pin "1") (pinfunction "1_1") (pintype "passive"))
    )
    (net (code "41") (name "Net-(IC1-XTAL2)") (class "Default")
      (node (ref "C2") (pin "2") (pinfunction "2_2") (pintype "passive"))
      (node (ref "IC1") (pin "12") (pinfunction "XTAL2_12") (pintype "bidirectional"))
      (node (ref "Q1") (pin "2") (pinfunction "2_2") (pintype "passive"))
    )
    (net (code "42") (name "Net-(IC2A-C1+)") (class "Default")
      (node (ref "C5") (pin "1") (pinfunction "1_1") (pintype "passive"))
      (node (ref "IC2") (pin "1") (pinfunction "C1+_1") (pintype "bidirectional"))
    )
    (net (code "43") (name "Net-(IC2A-C1-)") (class "Default")
      (node (ref "C5") (pin "2") (pinfunction "2_2") (pintype "passive"))
      (node (ref "IC2") (pin "3") (pinfunction "C1-_3") (pintype "bidirectional"))
    )
    (net (code "44") (name "Net-(IC2A-C2+)") (class "Default")
      (node (ref "C6") (pin "1") (pinfunction "1_1") (pintype "passive"))
      (node (ref "IC2") (pin "4") (pinfunction "C2+_4") (pintype "bidirectional"))
    )
    (net (code "45") (name "Net-(IC2A-C2-)") (class "Default")
      (node (ref "C6") (pin "2") (pinfunction "2_2") (pintype "passive"))
      (node (ref "IC2") (pin "5") (pinfunction "C2-_5") (pintype "bidirectional"))
    )
    (net (code "46") (name "Net-(IC2A-R1IN)") (class "Default")
      (node (ref "IC2") (pin "13") (pinfunction "R1IN_13") (pintype "input"))
      (node (ref "X4") (pin "3") (pinfunction "3_3") (pintype "passive"))
    )
    (net (code "47") (name "Net-(IC2A-T1OUT)") (class "Default")
      (node (ref "IC2") (pin "14") (pinfunction "T1OUT_14") (pintype "output"))
      (node (ref "X4") (pin "2") (pinfunction "2_2") (pintype "passive"))
    )
    (net (code "48") (name "Net-(IC2A-V+)") (class "Default")
      (node (ref "C7") (pin "1") (pinfunction "1_1") (pintype "passive"))
      (node (ref "IC2") (pin "2") (pinfunction "V+_2") (pintype "bidirectional"))
    )
    (net (code "49") (name "Net-(IC2A-V-)") (class "Default")
      (node (ref "C8") (pin "2") (pinfunction "2_2") (pintype "passive"))
      (node (ref "IC2") (pin "6") (pinfunction "V-_6") (pintype "bidirectional"))
    )
    (net (code "50") (name "Net-(IC4A-VOUT)") (class "Default")
      (node (ref "IC4") (pin "8") (pinfunction "VOUT_8") (pintype "output"))
      (node (ref "R5") (pin "2") (pinfunction "2_2") (pintype "passive"))
    )
    (net (code "51") (name "Net-(IC5A-VOUT)") (class "Default")
      (node (ref "IC5") (pin "8") (pinfunction "VOUT_8") (pintype "output"))
      (node (ref "R7") (pin "2") (pinfunction "2_2") (pintype "passive"))
    )
    (net (code "52") (name "Net-(IC6A-VOUT)") (class "Default")
      (node (ref "IC6") (pin "8") (pinfunction "VOUT_8") (pintype "output"))
      (node (ref "R9") (pin "2") (pinfunction "2_2") (pintype "passive"))
    )
    (net (code "53") (name "Net-(IC7A-VOUT)") (class "Default")
      (node (ref "IC7") (pin "8") (pinfunction "VOUT_8") (pintype "output"))
      (node (ref "R11") (pin "2") (pinfunction "2_2") (pintype "passive"))
    )
    (net (code "54") (name "Net-(IC8A-VOUT)") (class "Default")
      (node (ref "IC8") (pin "8") (pinfunction "VOUT_8") (pintype "output"))
      (node (ref "R13") (pin "2") (pinfunction "2_2") (pintype "passive"))
    )
    (net (code "55") (name "Net-(IC9A-VOUT)") (class "Default")
      (node (ref "IC9") (pin "8") (pinfunction "VOUT_8") (pintype "output"))
      (node (ref "R15") (pin "2") (pinfunction "2_2") (pintype "passive"))
    )
    (net (code "56") (name "Net-(IC10A-VOUT)") (class "Default")
      (node (ref "IC10") (pin "8") (pinfunction "VOUT_8") (pintype "output"))
      (node (ref "R17") (pin "2") (pinfunction "2_2") (pintype "passive"))
    )
    (net (code "57") (name "Net-(IC11A--IN)") (class "Default")
      (node (ref "IC11") (pin "2") (pinfunction "-IN_2") (pintype "input"))
      (node (ref "R4") (pin "1") (pinfunction "1_1") (pintype "passive"))
      (node (ref "R5") (pin "1") (pinfunction "1_1") (pintype "passive"))
    )
    (net (code "58") (name "Net-(IC11B--IN)") (class "Default")
      (node (ref "IC11") (pin "6") (pinfunction "-IN_6") (pintype "input"))
      (node (ref "R6") (pin "1") (pinfunction "1_1") (pintype "passive"))
      (node (ref "R7") (pin "1") (pinfunction "1_1") (pintype "passive"))
    )
    (net (code "59") (name "Net-(IC11C--IN)") (class "Default")
      (node (ref "IC11") (pin "9") (pinfunction "-IN_9") (pintype "input"))
      (node (ref "R8") (pin "1") (pinfunction "1_1") (pintype "passive"))
      (node (ref "R9") (pin "1") (pinfunction "1_1") (pintype "passive"))
    )
    (net (code "60") (name "Net-(IC11D--IN)") (class "Default")
      (node (ref "IC11") (pin "13") (pinfunction "-IN_13") (pintype "input"))
      (node (ref "R10") (pin "1") (pinfunction "1_1") (pintype "passive"))
      (node (ref "R11") (pin "1") (pinfunction "1_1") (pintype "passive"))
    )
    (net (code "61") (name "Net-(IC11E-V+)") (class "Default")
      (node (ref "C24") (pin "1") (pinfunction "1_1") (pintype "passive"))
      (node (ref "C25") (pin "1") (pinfunction "1_1") (pintype "passive"))
      (node (ref "IC11") (pin "4") (pinfunction "V+_4") (pintype "power_in"))
      (node (ref "IC12") (pin "4") (pinfunction "V+_4") (pintype "power_in"))
      (node (ref "T1") (pin "C") (pinfunction "C_C") (pintype "passive"))
    )
    (net (code "62") (name "Net-(IC12A--IN)") (class "Default")
      (node (ref "IC12") (pin "2") (pinfunction "-IN_2") (pintype "input"))
      (node (ref "R12") (pin "1") (pinfunction "1_1") (pintype "passive"))
      (node (ref "R13") (pin "1") (pinfunction "1_1") (pintype "passive"))
    )
    (net (code "63") (name "Net-(IC12B--IN)") (class "Default")
      (node (ref "IC12") (pin "6") (pinfunction "-IN_6") (pintype "input"))
      (node (ref "IC12") (pin "7") (pinfunction "OUT_7") (pintype "output"))
    )
    (net (code "64") (name "Net-(IC12C--IN)") (class "Default")
      (node (ref "IC12") (pin "9") (pinfunction "-IN_9") (pintype "input"))
      (node (ref "R16") (pin "1") (pinfunction "1_1") (pintype "passive"))
      (node (ref "R17") (pin "1") (pinfunction "1_1") (pintype "passive"))
    )
    (net (code "65") (name "Net-(IC12D--IN)") (class "Default")
      (node (ref "IC12") (pin "13") (pinfunction "-IN_13") (pintype "input"))
      (node (ref "R14") (pin "1") (pinfunction "1_1") (pintype "passive"))
      (node (ref "R15") (pin "1") (pinfunction "1_1") (pintype "passive"))
    )
    (net (code "66") (name "Net-(IC14-+IN)") (class "Default")
      (node (ref "IC14") (pin "3") (pinfunction "+IN_3") (pintype "input"))
      (node (ref "R38") (pin "2") (pinfunction "2_2") (pintype "passive"))
      (node (ref "R39") (pin "1") (pinfunction "1_1") (pintype "passive"))
    )
    (net (code "67") (name "Net-(IC14--IN)") (class "Default")
      (node (ref "IC14") (pin "4") (pinfunction "-IN_4") (pintype "input"))
      (node (ref "R18") (pin "1") (pinfunction "1_1") (pintype "passive"))
      (node (ref "R19") (pin "1") (pinfunction "1_1") (pintype "passive"))
    )
    (net (code "68") (name "Net-(IC15-+IN)") (class "Default")
      (node (ref "IC15") (pin "3") (pinfunction "+IN_3") (pintype "input"))
      (node (ref "R40") (pin "2") (pinfunction "2_2") (pintype "passive"))
      (node (ref "R41") (pin "1") (pinfunction "1_1") (pintype "passive"))
    )
    (net (code "69") (name "Net-(IC15--IN)") (class "Default")
      (node (ref "IC15") (pin "4") (pinfunction "-IN_4") (pintype "input"))
      (node (ref "R20") (pin "1") (pinfunction "1_1") (pintype "passive"))
      (node (ref "R21") (pin "1") (pinfunction "1_1") (pintype "passive"))
    )
    (net (code "70") (name "Net-(IC16-+IN)") (class "Default")
      (node (ref "IC16") (pin "3") (pinfunction "+IN_3") (pintype "input"))
      (node (ref "R42") (pin "1") (pinfunction "1_1") (pintype "passive"))
      (node (ref "R43") (pin "1") (pinfunction "1_1") (pintype "passive"))
    )
    (net (code "71") (name "Net-(IC16--IN)") (class "Default")
      (node (ref "IC16") (pin "4") (pinfunction "-IN_4") (pintype "input"))
      (node (ref "R22") (pin "1") (pinfunction "1_1") (pintype "passive"))
      (node (ref "R23") (pin "1") (pinfunction "1_1") (pintype "passive"))
    )
    (net (code "72") (name "Net-(IC17-+IN)") (class "Default")
      (node (ref "IC17") (pin "3") (pinfunction "+IN_3") (pintype "input"))
      (node (ref "R44") (pin "2") (pinfunction "2_2") (pintype "passive"))
      (node (ref "R45") (pin "1") (pinfunction "1_1") (pintype "passive"))
    )
    (net (code "73") (name "Net-(IC17--IN)") (class "Default")
      (node (ref "IC17") (pin "4") (pinfunction "-IN_4") (pintype "input"))
      (node (ref "R24") (pin "1") (pinfunction "1_1") (pintype "passive"))
      (node (ref "R25") (pin "1") (pinfunction "1_1") (pintype "passive"))
    )
    (net (code "74") (name "Net-(IC18-+IN)") (class "Default")
      (node (ref "IC18") (pin "3") (pinfunction "+IN_3") (pintype "input"))
      (node (ref "R46") (pin "1") (pinfunction "1_1") (pintype "passive"))
      (node (ref "R47") (pin "2") (pinfunction "2_2") (pintype "passive"))
    )
    (net (code "75") (name "Net-(IC18--IN)") (class "Default")
      (node (ref "IC18") (pin "4") (pinfunction "-IN_4") (pintype "input"))
      (node (ref "R26") (pin "1") (pinfunction "1_1") (pintype "passive"))
      (node (ref "R27") (pin "1") (pinfunction "1_1") (pintype "passive"))
    )
    (net (code "76") (name "Net-(IC19-+IN)") (class "Default")
      (node (ref "IC19") (pin "3") (pinfunction "+IN_3") (pintype "input"))
      (node (ref "R48") (pin "2") (pinfunction "2_2") (pintype "passive"))
      (node (ref "R49") (pin "1") (pinfunction "1_1") (pintype "passive"))
    )
    (net (code "77") (name "Net-(IC19--IN)") (class "Default")
      (node (ref "IC19") (pin "4") (pinfunction "-IN_4") (pintype "input"))
      (node (ref "R30") (pin "1") (pinfunction "1_1") (pintype "passive"))
      (node (ref "R31") (pin "1") (pinfunction "1_1") (pintype "passive"))
    )
    (net (code "78") (name "Net-(IC20-+IN)") (class "Default")
      (node (ref "IC20") (pin "3") (pinfunction "+IN_3") (pintype "input"))
      (node (ref "R50") (pin "2") (pinfunction "2_2") (pintype "passive"))
      (node (ref "R51") (pin "1") (pinfunction "1_1") (pintype "passive"))
    )
    (net (code "79") (name "Net-(IC20--IN)") (class "Default")
      (node (ref "IC20") (pin "4") (pinfunction "-IN_4") (pintype "input"))
      (node (ref "R32") (pin "1") (pinfunction "1_1") (pintype "passive"))
      (node (ref "R33") (pin "1") (pinfunction "1_1") (pintype "passive"))
    )
    (net (code "80") (name "Net-(L1-Pad1)") (class "Default")
      (node (ref "L1") (pin "1") (pinfunction "1_1") (pintype "passive"))
      (node (ref "X1") (pin "-1") (pinfunction "-1_-1") (pintype "passive"))
    )
    (net (code "81") (name "Net-(LED1-C)") (class "Default")
      (node (ref "LED1") (pin "3") (pinfunction "C_3") (pintype "passive"))
      (node (ref "R3") (pin "2") (pinfunction "2_2") (pintype "passive"))
    )
    (net (code "82") (name "Net-(R19-Pad2)") (class "Default")
      (node (ref "R19") (pin "2") (pinfunction "2_2") (pintype "passive"))
      (node (ref "SL4") (pin "2") (pinfunction "2_2") (pintype "passive"))
    )
    (net (code "83") (name "Net-(R21-Pad2)") (class "Default")
      (node (ref "R21") (pin "2") (pinfunction "2_2") (pintype "passive"))
      (node (ref "SL4") (pin "4") (pinfunction "4_4") (pintype "passive"))
    )
    (net (code "84") (name "Net-(R23-Pad2)") (class "Default")
      (node (ref "R23") (pin "2") (pinfunction "2_2") (pintype "passive"))
      (node (ref "SL5") (pin "1") (pinfunction "1_1") (pintype "passive"))
    )
    (net (code "85") (name "Net-(R25-Pad2)") (class "Default")
      (node (ref "R25") (pin "2") (pinfunction "2_2") (pintype "passive"))
      (node (ref "SL5") (pin "3") (pinfunction "3_3") (pintype "passive"))
    )
    (net (code "86") (name "Net-(R27-Pad2)") (class "Default")
      (node (ref "R27") (pin "2") (pinfunction "2_2") (pintype "passive"))
      (node (ref "SL5") (pin "5") (pinfunction "5_5") (pintype "passive"))
    )
    (net (code "87") (name "Net-(R29-Pad2)") (class "Default")
      (node (ref "R29") (pin "2") (pinfunction "2_2") (pintype "passive"))
      (node (ref "SL6") (pin "5") (pinfunction "5_5") (pintype "passive"))
    )
    (net (code "88") (name "Net-(R31-Pad2)") (class "Default")
      (node (ref "R31") (pin "2") (pinfunction "2_2") (pintype "passive"))
      (node (ref "SL6") (pin "2") (pinfunction "2_2") (pintype "passive"))
    )
    (net (code "89") (name "Net-(R33-Pad2)") (class "Default")
      (node (ref "R33") (pin "2") (pinfunction "2_2") (pintype "passive"))
      (node (ref "SL6") (pin "4") (pinfunction "4_4") (pintype "passive"))
    )
    (net (code "90") (name "Net-(R36-Pad2)") (class "Default")
      (node (ref "R36") (pin "2") (pinfunction "2_2") (pintype "passive"))
      (node (ref "T2") (pin "B") (pinfunction "B_B") (pintype "passive"))
    )
    (net (code "91") (name "Net-(R37-Pad1)") (class "Default")
      (node (ref "R37") (pin "1") (pinfunction "1_1") (pintype "passive"))
      (node (ref "T2") (pin "C") (pinfunction "C_C") (pintype "passive"))
    )
    (net (code "92") (name "Net-(R37-Pad2)") (class "Default")
      (node (ref "R37") (pin "2") (pinfunction "2_2") (pintype "passive"))
      (node (ref "T1") (pin "B") (pinfunction "B_B") (pintype "passive"))
    )
    (net (code "93") (name "Net-(R38-Pad1)") (class "Default")
      (node (ref "R38") (pin "1") (pinfunction "1_1") (pintype "passive"))
      (node (ref "SL4") (pin "1") (pinfunction "1_1") (pintype "passive"))
    )
    (net (code "94") (name "Net-(R40-Pad1)") (class "Default")
      (node (ref "R40") (pin "1") (pinfunction "1_1") (pintype "passive"))
      (node (ref "SL4") (pin "3") (pinfunction "3_3") (pintype "passive"))
    )
    (net (code "95") (name "Net-(R42-Pad2)") (class "Default")
      (node (ref "R42") (pin "2") (pinfunction "2_2") (pintype "passive"))
      (node (ref "SL4") (pin "5") (pinfunction "5_5") (pintype "passive"))
    )
    (net (code "96") (name "Net-(R44-Pad1)") (class "Default")
      (node (ref "R44") (pin "1") (pinfunction "1_1") (pintype "passive"))
      (node (ref "SL5") (pin "2") (pinfunction "2_2") (pintype "passive"))
    )
    (net (code "97") (name "Net-(R47-Pad1)") (class "Default")
      (node (ref "R47") (pin "1") (pinfunction "1_1") (pintype "passive"))
      (node (ref "SL5") (pin "4") (pinfunction "4_4") (pintype "passive"))
    )
    (net (code "98") (name "Net-(R48-Pad1)") (class "Default")
      (node (ref "R48") (pin "1") (pinfunction "1_1") (pintype "passive"))
      (node (ref "SL6") (pin "1") (pinfunction "1_1") (pintype "passive"))
    )
    (net (code "99") (name "Net-(R50-Pad1)") (class "Default")
      (node (ref "R50") (pin "1") (pinfunction "1_1") (pintype "passive"))
      (node (ref "SL6") (pin "3") (pinfunction "3_3") (pintype "passive"))
    )
    (net (code "100") (name "U") (class "Default")
      (node (ref "C28") (pin "1") (pinfunction "1_1") (pintype "passive"))
      (node (ref "IC1") (pin "40") (pinfunction "(ADC0)PA0_40") (pintype "bidirectional"))
      (node (ref "R28") (pin "1") (pinfunction "1_1") (pintype "passive"))
      (node (ref "R29") (pin "1") (pinfunction "1_1") (pintype "passive"))
    )
    (net (code "101") (name "VDD") (class "Default")
      (node (ref "C10") (pin "1") (pinfunction "1_1") (pintype "passive"))
      (node (ref "C11") (pin "1") (pinfunction "1_1") (pintype "passive"))
      (node (ref "C12") (pin "1") (pinfunction "1_1") (pintype "passive"))
      (node (ref "C13") (pin "1") (pinfunction "1_1") (pintype "passive"))
      (node (ref "C14") (pin "1") (pinfunction "1_1") (pintype "passive"))
      (node (ref "C15") (pin "1") (pinfunction "1_1") (pintype "passive"))
      (node (ref "C16") (pin "1") (pinfunction "1_1") (pintype "passive"))
      (node (ref "C17") (pin "1") (pinfunction "1_1") (pintype "passive"))
      (node (ref "C18") (pin "1") (pinfunction "1_1") (pintype "passive"))
      (node (ref "C19") (pin "1") (pinfunction "1_1") (pintype "passive"))
      (node (ref "C20") (pin "1") (pinfunction "1_1") (pintype "passive"))
      (node (ref "C21") (pin "1") (pinfunction "1_1") (pintype "passive"))
      (node (ref "C22") (pin "1") (pinfunction "1_1") (pintype "passive"))
      (node (ref "C23") (pin "1") (pinfunction "1_1") (pintype "passive"))
      (node (ref "C7") (pin "2") (pinfunction "2_2") (pintype "passive"))
      (node (ref "C9") (pin "1") (pinfunction "1_1") (pintype "passive"))
      (node (ref "IC10") (pin "1") (pinfunction "VCC_1") (pintype "power_in"))
      (node (ref "IC10") (pin "6") (pinfunction "VREF_6") (pintype "input"))
      (node (ref "IC13") (pin "OUT") (pinfunction "OUT_OUT") (pintype "passive"))
      (node (ref "IC14") (pin "6") (pinfunction "V+_6") (pintype "power_in"))
      (node (ref "IC15") (pin "6") (pinfunction "V+_6") (pintype "power_in"))
      (node (ref "IC16") (pin "6") (pinfunction "V+_6") (pintype "power_in"))
      (node (ref "IC17") (pin "6") (pinfunction "V+_6") (pintype "power_in"))
      (node (ref "IC18") (pin "6") (pinfunction "V+_6") (pintype "power_in"))
      (node (ref "IC19") (pin "6") (pinfunction "V+_6") (pintype "power_in"))
      (node (ref "IC2") (pin "16") (pinfunction "VCC_16") (pintype "power_in"))
      (node (ref "IC20") (pin "6") (pinfunction "V+_6") (pintype "power_in"))
      (node (ref "IC4") (pin "1") (pinfunction "VCC_1") (pintype "power_in"))
      (node (ref "IC4") (pin "6") (pinfunction "VREF_6") (pintype "input"))
      (node (ref "IC5") (pin "1") (pinfunction "VCC_1") (pintype "power_in"))
      (node (ref "IC5") (pin "6") (pinfunction "VREF_6") (pintype "input"))
      (node (ref "IC6") (pin "1") (pinfunction "VCC_1") (pintype "power_in"))
      (node (ref "IC6") (pin "6") (pinfunction "VREF_6") (pintype "input"))
      (node (ref "IC7") (pin "1") (pinfunction "VCC_1") (pintype "power_in"))
      (node (ref "IC7") (pin "6") (pinfunction "VREF_6") (pintype "input"))
      (node (ref "IC8") (pin "1") (pinfunction "VCC_1") (pintype "power_in"))
      (node (ref "IC8") (pin "6") (pinfunction "VREF_6") (pintype "input"))
      (node (ref "IC9") (pin "1") (pinfunction "VCC_1") (pintype "power_in"))
      (node (ref "IC9") (pin "6") (pinfunction "VREF_6") (pintype "input"))
      (node (ref "JP1") (pin "2") (pinfunction "2_2") (pintype "passive"))
      (node (ref "JP3") (pin "1") (pinfunction "1_1") (pintype "passive"))
      (node (ref "JP7") (pin "4") (pinfunction "4_4") (pintype "passive"))
      (node (ref "LED1") (pin "1") (pinfunction "A_1") (pintype "passive"))
      (node (ref "R1") (pin "1") (pinfunction "1_1") (pintype "passive"))
      (node (ref "R2") (pin "1") (pinfunction "1_1") (pintype "passive"))
    )
    (net (code "102") (name "VREF") (class "Default")
      (node (ref "IC11") (pin "10") (pinfunction "+IN_10") (pintype "input"))
      (node (ref "IC11") (pin "12") (pinfunction "+IN_12") (pintype "input"))
      (node (ref "IC11") (pin "3") (pinfunction "+IN_3") (pintype "input"))
      (node (ref "IC11") (pin "5") (pinfunction "+IN_5") (pintype "input"))
      (node (ref "IC12") (pin "10") (pinfunction "+IN_10") (pintype "input"))
      (node (ref "IC12") (pin "12") (pinfunction "+IN_12") (pintype "input"))
      (node (ref "IC12") (pin "3") (pinfunction "+IN_3") (pintype "input"))
      (node (ref "R34") (pin "2") (pinfunction "2_2") (pintype "passive"))
      (node (ref "R35") (pin "1") (pinfunction "1_1") (pintype "passive"))
    )
    (net (code "103") (name "unconnected-(IC1-(AIN0{slash}INT2)PB2-Pad3)") (class "Default")
      (node (ref "IC1") (pin "3") (pinfunction "(AIN0/INT2)PB2_3") (pintype "bidirectional"))
    )
    (net (code "104") (name "unconnected-(IC1-(AIN1{slash}OC0)PB3-Pad4)") (class "Default")
      (node (ref "IC1") (pin "4") (pinfunction "(AIN1/OC0)PB3_4") (pintype "bidirectional"))
    )
    (net (code "105") (name "unconnected-(IC1-(INT0)PD2-Pad16)") (class "Default")
      (node (ref "IC1") (pin "16") (pinfunction "(INT0)PD2_16") (pintype "bidirectional"))
    )
    (net (code "106") (name "unconnected-(IC1-(INT1)PD3-Pad17)") (class "Default")
      (node (ref "IC1") (pin "17") (pinfunction "(INT1)PD3_17") (pintype "bidirectional"))
    )
    (net (code "107") (name "unconnected-(IC1-(OC1B)PD4-Pad18)") (class "Default")
      (node (ref "IC1") (pin "18") (pinfunction "(OC1B)PD4_18") (pintype "bidirectional"))
    )
    (net (code "108") (name "unconnected-(IC1-(SS)PB4-Pad5)") (class "Default")
      (node (ref "IC1") (pin "5") (pinfunction "(SS)PB4_5") (pintype "bidirectional"))
    )
    (net (code "109") (name "unconnected-(IC2A-R2OUT-Pad9)") (class "Default")
      (node (ref "IC2") (pin "9") (pinfunction "R2OUT_9") (pintype "output"))
    )
    (net (code "110") (name "unconnected-(IC2A-T2OUT-Pad7)") (class "Default")
      (node (ref "IC2") (pin "7") (pinfunction "T2OUT_7") (pintype "output"))
    )
    (net (code "111") (name "unconnected-(X1-Pad-2)") (class "Default")
      (node (ref "X1") (pin "-2") (pinfunction "-2_-2") (pintype "passive"))
    )
    (net (code "112") (name "unconnected-(X2-Pad4)") (class "Default")
      (node (ref "X2") (pin "4") (pinfunction "4_4") (pintype "passive"))
    )
    (net (code "113") (name "unconnected-(X2-Pad5)") (class "Default")
      (node (ref "X2") (pin "5") (pinfunction "5_5") (pintype "passive"))
    )
    (net (code "114") (name "unconnected-(X3-Pad4)") (class "Default")
      (node (ref "X3") (pin "4") (pinfunction "4_4") (pintype "passive"))
    )
    (net (code "115") (name "unconnected-(X3-Pad5)") (class "Default")
      (node (ref "X3") (pin "5") (pinfunction "5_5") (pintype "passive"))
    )
    (net (code "116") (name "unconnected-(X4-Pad1)") (class "Default")
      (node (ref "X4") (pin "1") (pinfunction "1_1") (pintype "passive"))
    )
    (net (code "117") (name "unconnected-(X4-Pad4)") (class "Default")
      (node (ref "X4") (pin "4") (pinfunction "4_4") (pintype "passive"))
    )
    (net (code "118") (name "unconnected-(X4-Pad6)") (class "Default")
      (node (ref "X4") (pin "6") (pinfunction "6_6") (pintype "passive"))
    )
    (net (code "119") (name "unconnected-(X4-Pad7)") (class "Default")
      (node (ref "X4") (pin "7") (pinfunction "7_7") (pintype "passive"))
    )
    (net (code "120") (name "unconnected-(X4-Pad8)") (class "Default")
      (node (ref "X4") (pin "8") (pinfunction "8_8") (pintype "passive"))
    )
    (net (code "121") (name "unconnected-(X4-Pad9)") (class "Default")
      (node (ref "X4") (pin "9") (pinfunction "9_9") (pintype "passive"))
    )
  )
)
